# timetwister.net
KiCad netlist of a schematic drawn in EAGLE
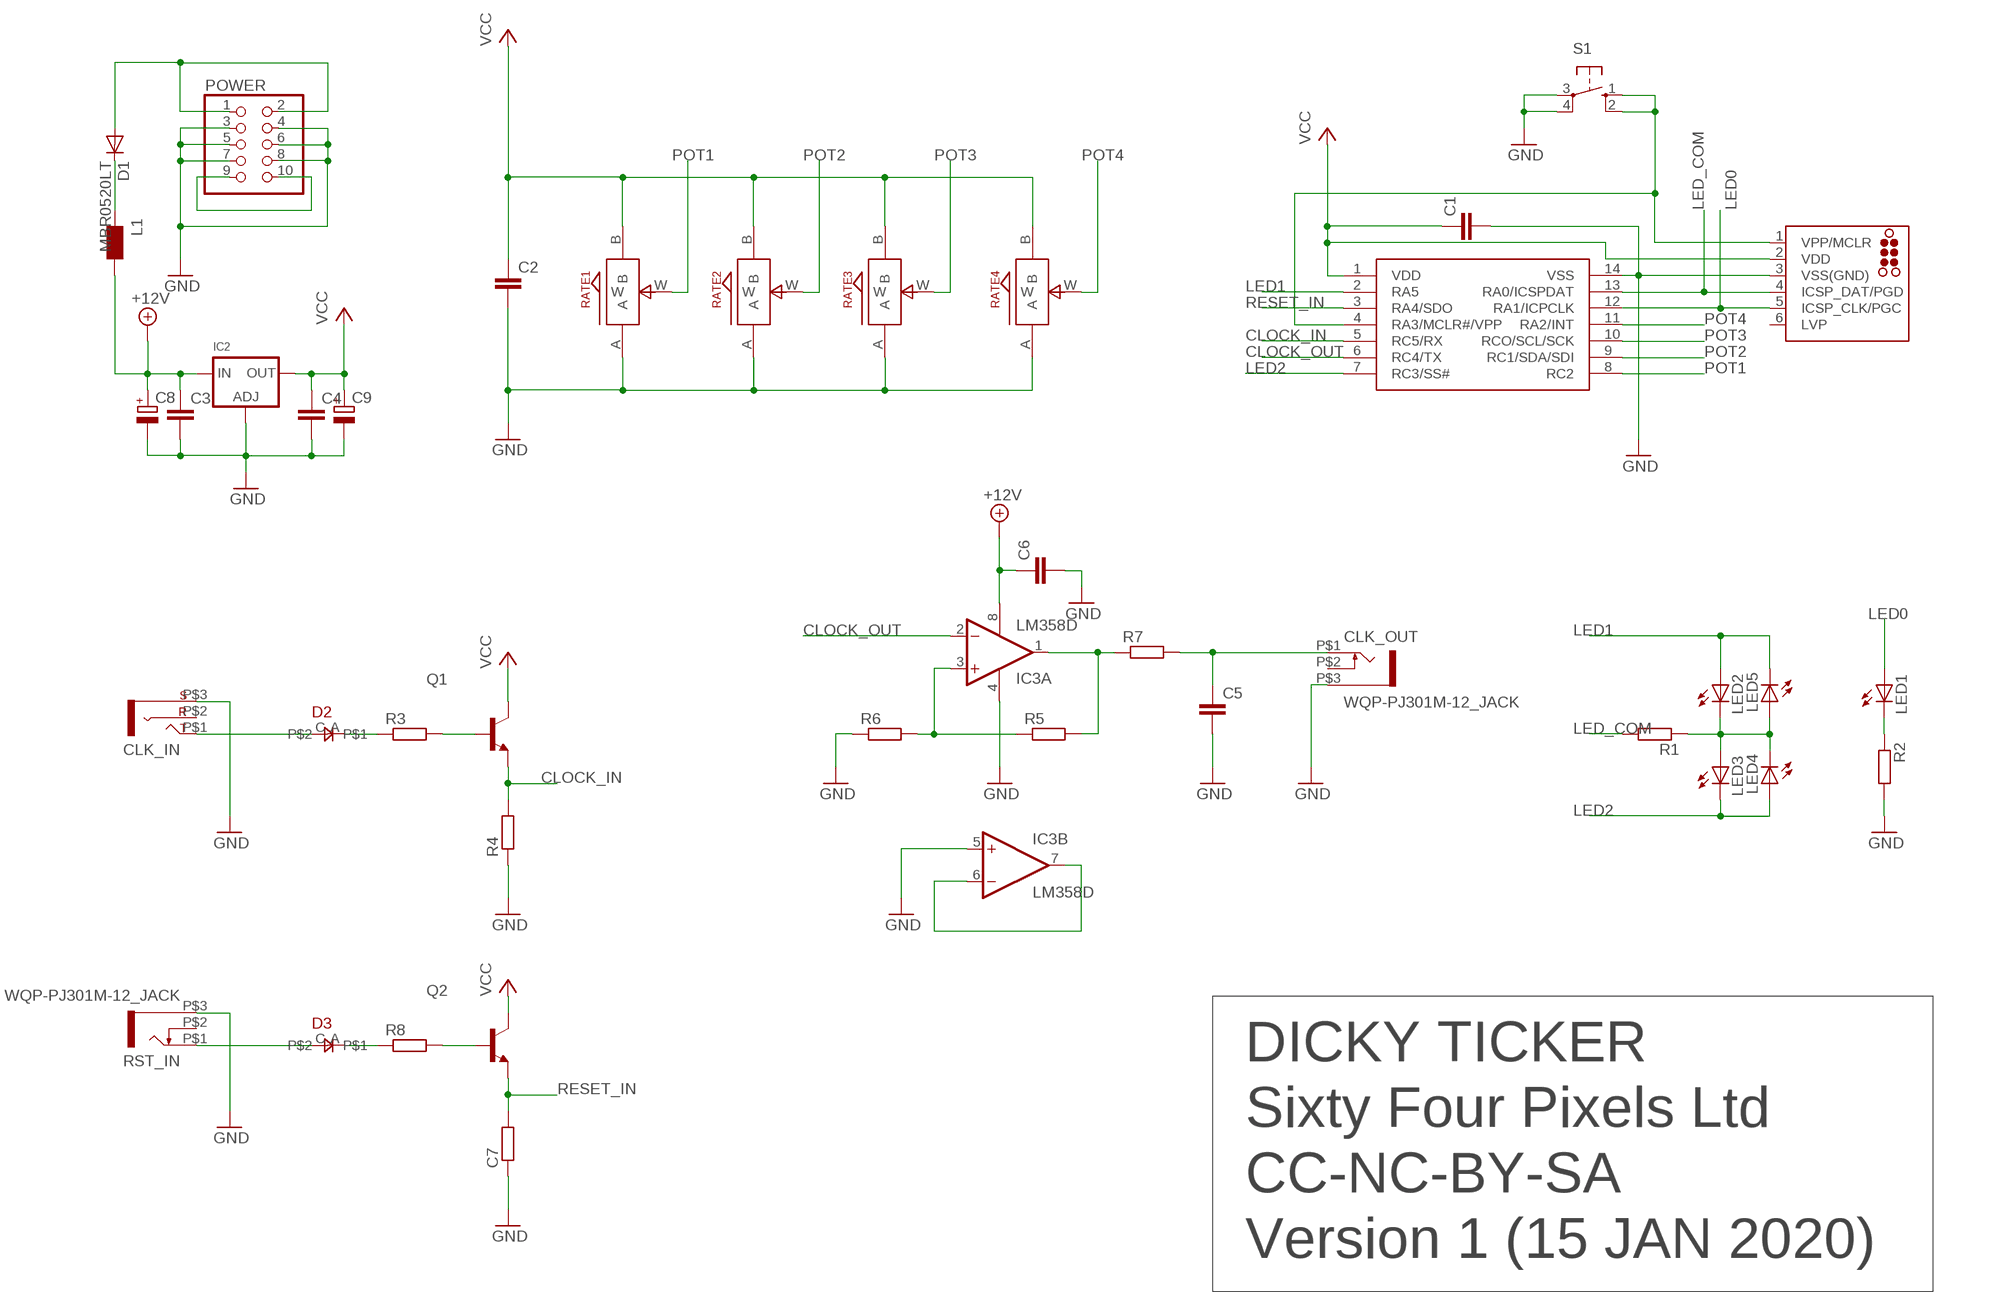
[diagram p0: schematic, sheet 1]

(export (version "E")
  (design (tool "Eeschema 10.0.6"))
  (components
    (comp (ref "C1")
      (value "C-EUC0805")
      (footprint "eagle-import:C0805")
      (libsource (lib "eagle-import") (part "C-EUC0805"))
    )
    (comp (ref "C2")
      (value "C-EUC0805")
      (footprint "eagle-import:C0805")
      (libsource (lib "eagle-import") (part "C-EUC0805"))
    )
    (comp (ref "C3")
      (value "C-EUC0805")
      (footprint "eagle-import:C0805")
      (libsource (lib "eagle-import") (part "C-EUC0805"))
    )
    (comp (ref "C4")
      (value "C-EUC0805")
      (footprint "eagle-import:C0805")
      (libsource (lib "eagle-import") (part "C-EUC0805"))
    )
    (comp (ref "C5")
      (value "C-EUC0805")
      (footprint "eagle-import:C0805")
      (libsource (lib "eagle-import") (part "C-EUC0805"))
    )
    (comp (ref "C6")
      (value "C-EUC0805")
      (footprint "eagle-import:C0805")
      (libsource (lib "eagle-import") (part "C-EUC0805"))
    )
    (comp (ref "C7")
      (value "R-EU_R0805")
      (footprint "eagle-import:R0805")
      (libsource (lib "eagle-import") (part "R-EU_R0805"))
    )
    (comp (ref "C8")
      (value "CPOL-EUE2-5")
      (footprint "eagle-import:E2-5")
      (libsource (lib "eagle-import") (part "CPOL-EUE2-5"))
    )
    (comp (ref "C9")
      (value "CPOL-EUE2-5")
      (footprint "eagle-import:E2-5")
      (libsource (lib "eagle-import") (part "CPOL-EUE2-5"))
    )
    (comp (ref "CLK_IN")
      (value "THONKICONN_STEREO")
      (footprint "eagle-import:WQP-PJ301M-ST")
      (libsource (lib "eagle-import") (part "THONKICONN_STEREO"))
    )
    (comp (ref "CLK_OUT")
      (value "WQP-PJ301M-12_JACK")
      (footprint "eagle-import:WQP-PJ301M-12_JACK")
      (libsource (lib "eagle-import") (part "WQP-PJ301M-12_JACK"))
    )
    (comp (ref "D1")
      (value "MBR0520LT")
      (footprint "eagle-import:SOD123")
      (libsource (lib "eagle-import") (part "MBR0520LT"))
    )
    (comp (ref "D2")
      (value "0805DIODE")
      (footprint "eagle-import:0805DIODE")
      (libsource (lib "eagle-import") (part "0805DIODE"))
    )
    (comp (ref "D3")
      (value "0805DIODE")
      (footprint "eagle-import:0805DIODE")
      (libsource (lib "eagle-import") (part "0805DIODE"))
    )
    (comp (ref "IC1")
      (value "PIC16F1825SO14")
      (footprint "eagle-import:SO14")
      (libsource (lib "eagle-import") (part "PIC16F1825SO14"))
    )
    (comp (ref "IC2")
      (value "LM1117SOT223-WAVE")
      (footprint "eagle-import:SOT223-W")
      (libsource (lib "eagle-import") (part "LM1117SOT223-WAVE"))
    )
    (comp (ref "IC3")
      (value "LM358D")
      (footprint "eagle-import:SO08")
      (libsource (lib "eagle-import") (part "LM358D"))
    )
    (comp (ref "ICSP")
      (value "TC2030-MCP-NL")
      (footprint "eagle-import:TC2030-MCP-NL")
      (libsource (lib "eagle-import") (part "TC2030-MCP-NL"))
    )
    (comp (ref "L1")
      (value "WE-CBF_0805")
      (footprint "eagle-import:0805")
      (libsource (lib "eagle-import") (part "WE-CBF_0805"))
    )
    (comp (ref "LED1")
      (value "LED3MM")
      (footprint "eagle-import:LED3MM")
      (libsource (lib "eagle-import") (part "LED3MM"))
    )
    (comp (ref "LED2")
      (value "LED3MM")
      (footprint "eagle-import:LED3MM")
      (libsource (lib "eagle-import") (part "LED3MM"))
    )
    (comp (ref "LED3")
      (value "LED3MM")
      (footprint "eagle-import:LED3MM")
      (libsource (lib "eagle-import") (part "LED3MM"))
    )
    (comp (ref "LED4")
      (value "LED3MM")
      (footprint "eagle-import:LED3MM")
      (libsource (lib "eagle-import") (part "LED3MM"))
    )
    (comp (ref "LED5")
      (value "LED3MM")
      (footprint "eagle-import:LED3MM")
      (libsource (lib "eagle-import") (part "LED3MM"))
    )
    (comp (ref "POWER")
      (value "PINHD-2X5")
      (footprint "eagle-import:2X05")
      (libsource (lib "eagle-import") (part "PINHD-2X5"))
    )
    (comp (ref "Q1")
      (value "MMBT3904LT1-NPN-SOT23-BEC")
      (footprint "eagle-import:SOT23-BEC")
      (libsource (lib "eagle-import") (part "-NPN-SOT23-BECMMBT3904LT1"))
    )
    (comp (ref "Q2")
      (value "MMBT3904LT1-NPN-SOT23-BEC")
      (footprint "eagle-import:SOT23-BEC")
      (libsource (lib "eagle-import") (part "-NPN-SOT23-BECMMBT3904LT1"))
    )
    (comp (ref "R1")
      (value "R-EU_R0805")
      (footprint "eagle-import:R0805")
      (libsource (lib "eagle-import") (part "R-EU_R0805"))
    )
    (comp (ref "R2")
      (value "R-EU_R0805")
      (footprint "eagle-import:R0805")
      (libsource (lib "eagle-import") (part "R-EU_R0805"))
    )
    (comp (ref "R3")
      (value "R-EU_R0805")
      (footprint "eagle-import:R0805")
      (libsource (lib "eagle-import") (part "R-EU_R0805"))
    )
    (comp (ref "R4")
      (value "R-EU_R0805")
      (footprint "eagle-import:R0805")
      (libsource (lib "eagle-import") (part "R-EU_R0805"))
    )
    (comp (ref "R5")
      (value "R-EU_R0805")
      (footprint "eagle-import:R0805")
      (libsource (lib "eagle-import") (part "R-EU_R0805"))
    )
    (comp (ref "R6")
      (value "R-EU_R0805")
      (footprint "eagle-import:R0805")
      (libsource (lib "eagle-import") (part "R-EU_R0805"))
    )
    (comp (ref "R7")
      (value "R-EU_R0805")
      (footprint "eagle-import:R0805")
      (libsource (lib "eagle-import") (part "R-EU_R0805"))
    )
    (comp (ref "R8")
      (value "R-EU_R0805")
      (footprint "eagle-import:R0805")
      (libsource (lib "eagle-import") (part "R-EU_R0805"))
    )
    (comp (ref "RATE1")
      (value "ALPS_POT_SMALL")
      (footprint "eagle-import:SMALL_ALPS_POT")
      (libsource (lib "eagle-import") (part "ALPS_POT_SMALL"))
    )
    (comp (ref "RATE2")
      (value "ALPS_POT_SMALL")
      (footprint "eagle-import:SMALL_ALPS_POT")
      (libsource (lib "eagle-import") (part "ALPS_POT_SMALL"))
    )
    (comp (ref "RATE3")
      (value "ALPS_POT_SMALL")
      (footprint "eagle-import:SMALL_ALPS_POT")
      (libsource (lib "eagle-import") (part "ALPS_POT_SMALL"))
    )
    (comp (ref "RATE4")
      (value "ALPS_POT_SMALL")
      (footprint "eagle-import:SMALL_ALPS_POT")
      (libsource (lib "eagle-import") (part "ALPS_POT_SMALL"))
    )
    (comp (ref "RST_IN")
      (value "WQP-PJ301M-12_JACK")
      (footprint "eagle-import:WQP-PJ301M-12_JACK")
      (libsource (lib "eagle-import") (part "WQP-PJ301M-12_JACK"))
    )
    (comp (ref "S1")
      (value "10-XX")
      (footprint "eagle-import:B3F-10XX")
      (fields (field (name "MPN") "B3F-1000"))
      (libsource (lib "eagle-import") (part "10-XX"))
    )
  )
  (nets
    (net (code "1") (name "+12V") (class "Default")
      (node (ref "C3") (pin "1") (pinfunction "1_1") (pintype "passive"))
      (node (ref "C6") (pin "1") (pinfunction "1_1") (pintype "passive"))
      (node (ref "C8") (pin "+") (pinfunction "+_+") (pintype "passive"))
      (node (ref "IC2") (pin "3") (pinfunction "IN_3") (pintype "input"))
      (node (ref "IC3") (pin "8") (pinfunction "V+_8") (pintype "power_in"))
      (node (ref "L1") (pin "2") (pinfunction "2_2") (pintype "passive"))
    )
    (net (code "2") (name "/CLOCK_IN") (class "Default")
      (node (ref "IC1") (pin "5") (pinfunction "RC5/RX_5") (pintype "bidirectional"))
      (node (ref "Q1") (pin "E") (pinfunction "E_E") (pintype "passive"))
      (node (ref "R4") (pin "2") (pinfunction "2_2") (pintype "passive"))
    )
    (net (code "3") (name "/CLOCK_OUT") (class "Default")
      (node (ref "IC1") (pin "6") (pinfunction "RC4/TX_6") (pintype "bidirectional"))
      (node (ref "IC3") (pin "2") (pinfunction "-IN_2") (pintype "input"))
    )
    (net (code "4") (name "/LED0") (class "Default")
      (node (ref "IC1") (pin "12") (pinfunction "RA1/ICPCLK_12") (pintype "bidirectional"))
      (node (ref "ICSP") (pin "5") (pinfunction "ICSP_CLK/PGC_5") (pintype "output"))
      (node (ref "LED1") (pin "A") (pinfunction "A_A") (pintype "passive"))
    )
    (net (code "5") (name "/LED1") (class "Default")
      (node (ref "IC1") (pin "2") (pinfunction "RA5_2") (pintype "bidirectional"))
      (node (ref "LED2") (pin "A") (pinfunction "A_A") (pintype "passive"))
      (node (ref "LED5") (pin "K") (pinfunction "C_K") (pintype "passive"))
    )
    (net (code "6") (name "/LED2") (class "Default")
      (node (ref "IC1") (pin "7") (pinfunction "RC3/SS#_7") (pintype "bidirectional"))
      (node (ref "LED3") (pin "K") (pinfunction "C_K") (pintype "passive"))
      (node (ref "LED4") (pin "A") (pinfunction "A_A") (pintype "passive"))
    )
    (net (code "7") (name "/LED_COM") (class "Default")
      (node (ref "IC1") (pin "13") (pinfunction "RA0/ICSPDAT_13") (pintype "bidirectional"))
      (node (ref "ICSP") (pin "4") (pinfunction "ICSP_DAT/PGD_4") (pintype "bidirectional"))
      (node (ref "R1") (pin "2") (pinfunction "2_2") (pintype "passive"))
    )
    (net (code "8") (name "/POT1") (class "Default")
      (node (ref "IC1") (pin "8") (pinfunction "RC2_8") (pintype "bidirectional"))
      (node (ref "RATE1") (pin "W") (pinfunction "W_W") (pintype "bidirectional"))
    )
    (net (code "9") (name "/POT2") (class "Default")
      (node (ref "IC1") (pin "9") (pinfunction "RC1/SDA/SDI_9") (pintype "bidirectional"))
      (node (ref "RATE2") (pin "W") (pinfunction "W_W") (pintype "bidirectional"))
    )
    (net (code "10") (name "/POT3") (class "Default")
      (node (ref "IC1") (pin "10") (pinfunction "RCO/SCL/SCK_10") (pintype "bidirectional"))
      (node (ref "RATE3") (pin "W") (pinfunction "W_W") (pintype "bidirectional"))
    )
    (net (code "11") (name "/POT4") (class "Default")
      (node (ref "IC1") (pin "11") (pinfunction "RA2/INT_11") (pintype "bidirectional"))
      (node (ref "RATE4") (pin "W") (pinfunction "W_W") (pintype "bidirectional"))
    )
    (net (code "12") (name "/RESET_IN") (class "Default")
      (node (ref "C7") (pin "2") (pinfunction "2_2") (pintype "passive"))
      (node (ref "IC1") (pin "3") (pinfunction "RA4/SDO_3") (pintype "bidirectional"))
      (node (ref "Q2") (pin "E") (pinfunction "E_E") (pintype "passive"))
    )
    (net (code "13") (name "GND") (class "Default")
      (node (ref "C1") (pin "2") (pinfunction "2_2") (pintype "passive"))
      (node (ref "C2") (pin "2") (pinfunction "2_2") (pintype "passive"))
      (node (ref "C3") (pin "2") (pinfunction "2_2") (pintype "passive"))
      (node (ref "C4") (pin "2") (pinfunction "2_2") (pintype "passive"))
      (node (ref "C5") (pin "2") (pinfunction "2_2") (pintype "passive"))
      (node (ref "C6") (pin "2") (pinfunction "2_2") (pintype "passive"))
      (node (ref "C7") (pin "1") (pinfunction "1_1") (pintype "passive"))
      (node (ref "C8") (pin "-") (pinfunction "-_-") (pintype "passive"))
      (node (ref "C9") (pin "-") (pinfunction "-_-") (pintype "passive"))
      (node (ref "CLK_IN") (pin "P$3") (pinfunction "S_P$3") (pintype "passive"))
      (node (ref "CLK_OUT") (pin "P$3") (pinfunction "1_P$3") (pintype "passive"))
      (node (ref "IC1") (pin "14") (pinfunction "VSS_14") (pintype "power_in"))
      (node (ref "IC2") (pin "1") (pinfunction "ADJ_1") (pintype "input"))
      (node (ref "IC3") (pin "4") (pinfunction "V-_4") (pintype "power_in"))
      (node (ref "IC3") (pin "5") (pinfunction "+IN_5") (pintype "input"))
      (node (ref "ICSP") (pin "3") (pinfunction "VSS(GND)_3") (pintype "power_in"))
      (node (ref "POWER") (pin "3") (pinfunction "3_3") (pintype "passive"))
      (node (ref "POWER") (pin "4") (pinfunction "4_4") (pintype "passive"))
      (node (ref "POWER") (pin "5") (pinfunction "5_5") (pintype "passive"))
      (node (ref "POWER") (pin "6") (pinfunction "6_6") (pintype "passive"))
      (node (ref "POWER") (pin "7") (pinfunction "7_7") (pintype "passive"))
      (node (ref "POWER") (pin "8") (pinfunction "8_8") (pintype "passive"))
      (node (ref "R2") (pin "2") (pinfunction "2_2") (pintype "passive"))
      (node (ref "R4") (pin "1") (pinfunction "1_1") (pintype "passive"))
      (node (ref "R6") (pin "1") (pinfunction "1_1") (pintype "passive"))
      (node (ref "RATE1") (pin "A") (pinfunction "A_A") (pintype "bidirectional"))
      (node (ref "RATE2") (pin "A") (pinfunction "A_A") (pintype "bidirectional"))
      (node (ref "RATE3") (pin "A") (pinfunction "A_A") (pintype "bidirectional"))
      (node (ref "RATE4") (pin "A") (pinfunction "A_A") (pintype "bidirectional"))
      (node (ref "RST_IN") (pin "P$3") (pinfunction "1_P$3") (pintype "passive"))
      (node (ref "S1") (pin "3") (pinfunction "P_3") (pintype "passive"))
      (node (ref "S1") (pin "4") (pinfunction "P1_4") (pintype "passive"))
    )
    (net (code "14") (name "Net-(CLK_IN-T)") (class "Default")
      (node (ref "CLK_IN") (pin "P$1") (pinfunction "T_P$1") (pintype "passive"))
      (node (ref "D2") (pin "C") (pinfunction "P$1_C") (pintype "bidirectional"))
    )
    (net (code "15") (name "Net-(CLK_OUT-2)") (class "Default")
      (node (ref "C5") (pin "1") (pinfunction "1_1") (pintype "passive"))
      (node (ref "CLK_OUT") (pin "P$1") (pinfunction "2_P$1") (pintype "passive"))
      (node (ref "R7") (pin "2") (pinfunction "2_2") (pintype "passive"))
    )
    (net (code "16") (name "Net-(D1-PadA)") (class "Default")
      (node (ref "D1") (pin "A") (pinfunction "A_A") (pintype "passive"))
      (node (ref "POWER") (pin "1") (pinfunction "1_1") (pintype "passive"))
      (node (ref "POWER") (pin "2") (pinfunction "2_2") (pintype "passive"))
    )
    (net (code "17") (name "Net-(D1-PadC)") (class "Default")
      (node (ref "D1") (pin "C") (pinfunction "C_C") (pintype "passive"))
      (node (ref "L1") (pin "1") (pinfunction "1_1") (pintype "passive"))
    )
    (net (code "18") (name "Net-(D2-P$2)") (class "Default")
      (node (ref "D2") (pin "A") (pinfunction "P$2_A") (pintype "bidirectional"))
      (node (ref "R3") (pin "1") (pinfunction "1_1") (pintype "passive"))
    )
    (net (code "19") (name "Net-(D3-P$1)") (class "Default")
      (node (ref "D3") (pin "C") (pinfunction "P$1_C") (pintype "bidirectional"))
      (node (ref "RST_IN") (pin "P$1") (pinfunction "2_P$1") (pintype "passive"))
    )
    (net (code "20") (name "Net-(D3-P$2)") (class "Default")
      (node (ref "D3") (pin "A") (pinfunction "P$2_A") (pintype "bidirectional"))
      (node (ref "R8") (pin "1") (pinfunction "1_1") (pintype "passive"))
    )
    (net (code "21") (name "Net-(IC1-RA3{slash}MCLR#{slash}VPP)") (class "Default")
      (node (ref "IC1") (pin "4") (pinfunction "RA3/MCLR#/VPP_4") (pintype "input"))
      (node (ref "ICSP") (pin "1") (pinfunction "VPP/MCLR_1") (pintype "passive"))
      (node (ref "S1") (pin "1") (pinfunction "S_1") (pintype "passive"))
      (node (ref "S1") (pin "2") (pinfunction "S1_2") (pintype "passive"))
    )
    (net (code "22") (name "Net-(IC3A-+IN)") (class "Default")
      (node (ref "IC3") (pin "3") (pinfunction "+IN_3") (pintype "input"))
      (node (ref "R5") (pin "1") (pinfunction "1_1") (pintype "passive"))
      (node (ref "R6") (pin "2") (pinfunction "2_2") (pintype "passive"))
    )
    (net (code "23") (name "Net-(IC3A-OUT)") (class "Default")
      (node (ref "IC3") (pin "1") (pinfunction "OUT_1") (pintype "output"))
      (node (ref "R5") (pin "2") (pinfunction "2_2") (pintype "passive"))
      (node (ref "R7") (pin "1") (pinfunction "1_1") (pintype "passive"))
    )
    (net (code "24") (name "Net-(IC3B--IN)") (class "Default")
      (node (ref "IC3") (pin "6") (pinfunction "-IN_6") (pintype "input"))
      (node (ref "IC3") (pin "7") (pinfunction "OUT_7") (pintype "output"))
    )
    (net (code "25") (name "Net-(LED1-C)") (class "Default")
      (node (ref "LED1") (pin "K") (pinfunction "C_K") (pintype "passive"))
      (node (ref "R2") (pin "1") (pinfunction "1_1") (pintype "passive"))
    )
    (net (code "26") (name "Net-(LED2-C)") (class "Default")
      (node (ref "LED2") (pin "K") (pinfunction "C_K") (pintype "passive"))
      (node (ref "LED3") (pin "A") (pinfunction "A_A") (pintype "passive"))
      (node (ref "LED4") (pin "K") (pinfunction "C_K") (pintype "passive"))
      (node (ref "LED5") (pin "A") (pinfunction "A_A") (pintype "passive"))
      (node (ref "R1") (pin "1") (pinfunction "1_1") (pintype "passive"))
    )
    (net (code "27") (name "Net-(POWER-Pad10)") (class "Default")
      (node (ref "POWER") (pin "10") (pinfunction "10_10") (pintype "passive"))
      (node (ref "POWER") (pin "9") (pinfunction "9_9") (pintype "passive"))
    )
    (net (code "28") (name "Net-(Q1-PadB)") (class "Default")
      (node (ref "Q1") (pin "B") (pinfunction "B_B") (pintype "passive"))
      (node (ref "R3") (pin "2") (pinfunction "2_2") (pintype "passive"))
    )
    (net (code "29") (name "Net-(Q2-PadB)") (class "Default")
      (node (ref "Q2") (pin "B") (pinfunction "B_B") (pintype "passive"))
      (node (ref "R8") (pin "2") (pinfunction "2_2") (pintype "passive"))
    )
    (net (code "30") (name "VCC") (class "Default")
      (node (ref "C1") (pin "1") (pinfunction "1_1") (pintype "passive"))
      (node (ref "C2") (pin "1") (pinfunction "1_1") (pintype "passive"))
      (node (ref "C4") (pin "1") (pinfunction "1_1") (pintype "passive"))
      (node (ref "C9") (pin "+") (pinfunction "+_+") (pintype "passive"))
      (node (ref "IC1") (pin "1") (pinfunction "VDD_1") (pintype "power_in"))
      (node (ref "IC2") (pin "2") (pinfunction "OUT_2") (pintype "passive"))
      (node (ref "ICSP") (pin "2") (pinfunction "VDD_2") (pintype "power_in"))
      (node (ref "Q1") (pin "C") (pinfunction "C_C") (pintype "passive"))
      (node (ref "Q2") (pin "C") (pinfunction "C_C") (pintype "passive"))
      (node (ref "RATE1") (pin "B") (pinfunction "B_B") (pintype "bidirectional"))
      (node (ref "RATE2") (pin "B") (pinfunction "B_B") (pintype "bidirectional"))
      (node (ref "RATE3") (pin "B") (pinfunction "B_B") (pintype "bidirectional"))
      (node (ref "RATE4") (pin "B") (pinfunction "B_B") (pintype "bidirectional"))
    )
    (net (code "31") (name "unconnected-(CLK_IN-R-PadP$2)") (class "Default")
      (node (ref "CLK_IN") (pin "P$2") (pinfunction "R_P$2") (pintype "passive"))
    )
    (net (code "32") (name "unconnected-(CLK_OUT-3-PadP$2)") (class "Default")
      (node (ref "CLK_OUT") (pin "P$2") (pinfunction "3_P$2") (pintype "passive"))
    )
    (net (code "33") (name "unconnected-(ICSP-LVP-Pad6)") (class "Default")
      (node (ref "ICSP") (pin "6") (pinfunction "LVP_6") (pintype "bidirectional"))
    )
    (net (code "34") (name "unconnected-(RST_IN-3-PadP$2)") (class "Default")
      (node (ref "RST_IN") (pin "P$2") (pinfunction "3_P$2") (pintype "passive"))
    )
  )
)
